# Capteurs.net
KiCad netlist of a schematic drawn in Altium Designer
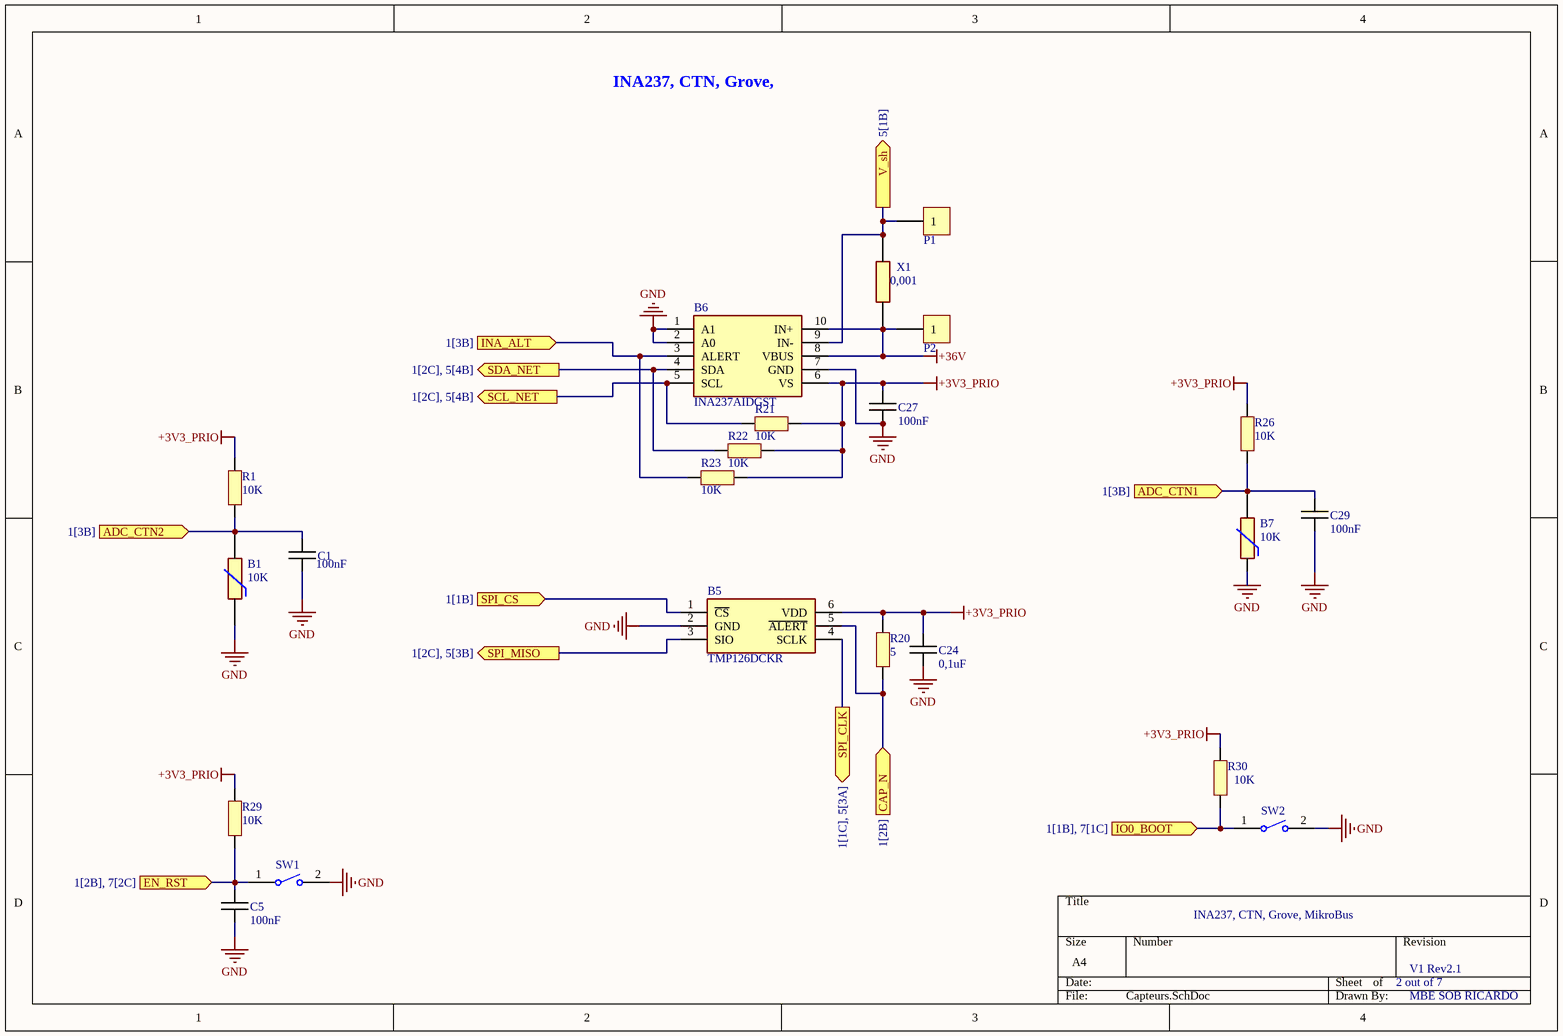
[diagram p0: Capteurs.SchDoc]

(export (version "E")
  (design (tool "Eeschema 10.0.6"))
  (components
    (comp (ref "B1")
      (value "10K")
      (footprint "RESC2212X50N")
      (description "NTC SMD Thermistor, NB12K, 10K, 5% AVX 10k 0805 Protection NTC Thermistor, 5s, 2 x 1.25 x 1.3mm")
      (fields
        (field (name "MANUFACTURER_PART_NUMBER") "NB12K00103JBB")
        (field (name "MOUSER PART NUMBER") "581-NB12K00103JBB")
      )
      (libsource (lib "SCHLibrary") (part "NB12K00103JBB"))
    )
    (comp (ref "B5")
      (value "TMP126DCKR")
      (footprint "SOT65P210X110-6N")
      (fields (field (name "MOUSER PART NUMBER") "595-TMP126DCKR"))
      (libsource (lib "SCHLibrary") (part "TMP126DCKR"))
    )
    (comp (ref "B6")
      (value "INA237AIDGST")
      (footprint "SOP50P490X110-10N")
      (fields (field (name "MOUSER PART NUMBER") "595-INA237AIDGST"))
      (libsource (lib "SCHLibrary") (part "INA237AIDGST"))
    )
    (comp (ref "B7")
      (value "10K")
      (footprint "RESC2212X50N")
      (description "NTC SMD Thermistor, NB12K, 10K, 5% AVX 10k 0805 Protection NTC Thermistor, 5s, 2 x 1.25 x 1.3mm")
      (fields
        (field (name "MANUFACTURER_PART_NUMBER") "NB12K00103JBB")
        (field (name "MOUSER PART NUMBER") "581-NB12K00103JBB")
      )
      (libsource (lib "SCHLibrary") (part "NB12K00103JBB"))
    )
    (comp (ref "C1")
      (value "100nF")
      (footprint "CAPC1005X06N")
      (libsource (lib "SCHLibrary") (part "Capacitor"))
    )
    (comp (ref "C5")
      (value "100nF")
      (footprint "CAPC1005X06N")
      (libsource (lib "SCHLibrary") (part "Capacitor"))
    )
    (comp (ref "C24")
      (value "0,1uF")
      (footprint "CAPC1005X06N")
      (libsource (lib "SCHLibrary") (part "Capacitor"))
    )
    (comp (ref "C27")
      (value "100nF")
      (footprint "CAPC1005X06N")
      (libsource (lib "SCHLibrary") (part "Capacitor"))
    )
    (comp (ref "C29")
      (value "100nF")
      (footprint "CAPC1005X06N")
      (libsource (lib "SCHLibrary") (part "Capacitor"))
    )
    (comp (ref "P1")
      (value "Plage CMS 10x5")
      (footprint "Plage CMS 10x5")
      (description "Plage de report CMS 10x5mm")
      (libsource (lib "SCHLibrary") (part "Plage CMS 10x5"))
    )
    (comp (ref "P2")
      (value "Plage CMS 10x5")
      (footprint "Plage CMS 10x5")
      (description "Plage de report CMS 10x5mm")
      (libsource (lib "SCHLibrary") (part "Plage CMS 10x5"))
    )
    (comp (ref "R1") (value "10K") (footprint "RESC1005X06N") (libsource (lib "") (part "Resistor_2")))
    (comp (ref "R20") (value "5") (footprint "RESC1005X06N") (libsource (lib "") (part "Resistor_2")))
    (comp (ref "R21")
      (value "10K")
      (footprint "RESC1005X06N")
      (libsource (lib "SCHLibrary") (part "Resistor"))
    )
    (comp (ref "R22")
      (value "10K")
      (footprint "RESC1005X06N")
      (libsource (lib "SCHLibrary") (part "Resistor"))
    )
    (comp (ref "R23")
      (value "10K")
      (footprint "RESC1005X06N")
      (libsource (lib "SCHLibrary") (part "Resistor"))
    )
    (comp (ref "R26") (value "10K") (footprint "RESC1005X06N") (libsource (lib "") (part "Resistor_2")))
    (comp (ref "R29") (value "10K") (footprint "RESC1005X06N") (libsource (lib "") (part "Resistor_1")))
    (comp (ref "R30") (value "10K") (footprint "RESC1005X06N") (libsource (lib "") (part "Resistor_1")))
    (comp (ref "SW1")
      (value "FSMSM")
      (footprint "TECO-FSMSM-2_V")
      (description "FSMSM Push Button Switch, 50 mA, -35 to 85 degC, 2-Pin SMD, RoHS, Bulk")
      (fields (field (name "MANUFACTURER") "TE Connectivity"))
      (libsource (lib "SCHLibrary") (part "CMP-2000-07511-1"))
    )
    (comp (ref "SW2")
      (value "FSMSM")
      (footprint "TECO-FSMSM-2_V")
      (description "FSMSM Push Button Switch, 50 mA, -35 to 85 degC, 2-Pin SMD, RoHS, Bulk")
      (fields (field (name "MANUFACTURER") "TE Connectivity"))
      (libsource (lib "SCHLibrary") (part "CMP-2000-07511-1"))
    )
    (comp (ref "X1")
      (value "0,001")
      (footprint "RESC10052X200N")
      (fields
        (field (name "MANUFACTURER_PART_NUMBER") "PSR400ITQFF0L50")
        (field (name "MOUSER PART NUMBER") "755-PSR400ITQFF0L50")
      )
      (libsource (lib "SCHLibrary") (part "PSR400ITQFF0L50"))
    )
  )
  (nets
    (net (code "1") (name "+3V3_PRIO") (class "Default")
      (node (ref "B5") (pin "6") (pinfunction "VDD_6") (pintype "passive"))
      (node (ref "B6") (pin "6") (pinfunction "VS_6") (pintype "passive"))
      (node (ref "C24") (pin "1") (pinfunction "1_1") (pintype "passive"))
      (node (ref "C27") (pin "2") (pinfunction "2_2") (pintype "passive"))
      (node (ref "R1") (pin "2") (pinfunction "2_2") (pintype "passive"))
      (node (ref "R20") (pin "2") (pinfunction "2_2") (pintype "passive"))
      (node (ref "R21") (pin "1") (pinfunction "1_1") (pintype "passive"))
      (node (ref "R22") (pin "1") (pinfunction "1_1") (pintype "passive"))
      (node (ref "R23") (pin "1") (pinfunction "1_1") (pintype "passive"))
      (node (ref "R26") (pin "2") (pinfunction "2_2") (pintype "passive"))
      (node (ref "R29") (pin "1") (pinfunction "1_1") (pintype "passive"))
      (node (ref "R30") (pin "1") (pinfunction "1_1") (pintype "passive"))
    )
    (net (code "2") (name "+36V") (class "Default")
      (node (ref "B6") (pin "10") (pinfunction "IN+_10") (pintype "passive"))
      (node (ref "B6") (pin "8") (pinfunction "VBUS_8") (pintype "passive"))
      (node (ref "P2") (pin "1") (pinfunction "1_1") (pintype "passive"))
      (node (ref "X1") (pin "1") (pinfunction "1_1") (pintype "passive"))
    )
    (net (code "3") (name "/ADC_CTN1") (class "Default")
      (node (ref "B7") (pin "2") (pinfunction "2_2") (pintype "passive"))
      (node (ref "C29") (pin "2") (pinfunction "2_2") (pintype "passive"))
      (node (ref "R26") (pin "1") (pinfunction "1_1") (pintype "passive"))
    )
    (net (code "4") (name "/ADC_CTN2") (class "Default")
      (node (ref "B1") (pin "2") (pinfunction "2_2") (pintype "passive"))
      (node (ref "C1") (pin "1") (pinfunction "1_1") (pintype "passive"))
      (node (ref "R1") (pin "1") (pinfunction "1_1") (pintype "passive"))
    )
    (net (code "5") (name "/CAP_N") (class "Default")
      (node (ref "B5") (pin "5") (pinfunction "~{ALERT}_5") (pintype "passive"))
      (node (ref "R20") (pin "1") (pinfunction "1_1") (pintype "passive"))
    )
    (net (code "6") (name "/EN_RST") (class "Default")
      (node (ref "C5") (pin "2") (pinfunction "2_2") (pintype "passive"))
      (node (ref "R29") (pin "2") (pinfunction "2_2") (pintype "passive"))
      (node (ref "SW1") (pin "1") (pinfunction "1_1") (pintype "passive"))
    )
    (net (code "7") (name "/INA_ALT") (class "Default")
      (node (ref "B6") (pin "3") (pinfunction "ALERT_3") (pintype "passive"))
      (node (ref "R23") (pin "2") (pinfunction "2_2") (pintype "passive"))
    )
    (net (code "8") (name "/IO0_BOOT") (class "Default")
      (node (ref "R30") (pin "2") (pinfunction "2_2") (pintype "passive"))
      (node (ref "SW2") (pin "1") (pinfunction "1_1") (pintype "passive"))
    )
    (net (code "9") (name "/SCL_NET") (class "Default")
      (node (ref "B6") (pin "5") (pinfunction "SCL_5") (pintype "passive"))
      (node (ref "R21") (pin "2") (pinfunction "2_2") (pintype "passive"))
    )
    (net (code "10") (name "/SDA_NET") (class "Default")
      (node (ref "B6") (pin "4") (pinfunction "SDA_4") (pintype "passive"))
      (node (ref "R22") (pin "2") (pinfunction "2_2") (pintype "passive"))
    )
    (net (code "11") (name "/SPI_CLK") (class "Default")
      (node (ref "B5") (pin "4") (pinfunction "SCLK_4") (pintype "passive"))
    )
    (net (code "12") (name "/SPI_CS") (class "Default")
      (node (ref "B5") (pin "1") (pinfunction "~{CS}_1") (pintype "passive"))
    )
    (net (code "13") (name "/SPI_MISO") (class "Default")
      (node (ref "B5") (pin "3") (pinfunction "SIO_3") (pintype "passive"))
    )
    (net (code "14") (name "/V_sh") (class "Default")
      (node (ref "B6") (pin "9") (pinfunction "IN-_9") (pintype "passive"))
      (node (ref "P1") (pin "1") (pinfunction "1_1") (pintype "passive"))
      (node (ref "X1") (pin "2") (pinfunction "2_2") (pintype "passive"))
    )
    (net (code "15") (name "GND") (class "Default")
      (node (ref "B1") (pin "1") (pinfunction "1_1") (pintype "passive"))
      (node (ref "B5") (pin "2") (pinfunction "GND_2") (pintype "passive"))
      (node (ref "B6") (pin "1") (pinfunction "A1_1") (pintype "passive"))
      (node (ref "B6") (pin "2") (pinfunction "A0_2") (pintype "passive"))
      (node (ref "B6") (pin "7") (pinfunction "GND_7") (pintype "passive"))
      (node (ref "B7") (pin "1") (pinfunction "1_1") (pintype "passive"))
      (node (ref "C1") (pin "2") (pinfunction "2_2") (pintype "passive"))
      (node (ref "C24") (pin "2") (pinfunction "2_2") (pintype "passive"))
      (node (ref "C27") (pin "1") (pinfunction "1_1") (pintype "passive"))
      (node (ref "C29") (pin "1") (pinfunction "1_1") (pintype "passive"))
      (node (ref "C5") (pin "1") (pinfunction "1_1") (pintype "passive"))
      (node (ref "SW1") (pin "2") (pinfunction "2_2") (pintype "passive"))
      (node (ref "SW2") (pin "2") (pinfunction "2_2") (pintype "passive"))
    )
  )
)
